# PRE_amp_22_5.net
KiCad netlist of a schematic drawn in EAGLE
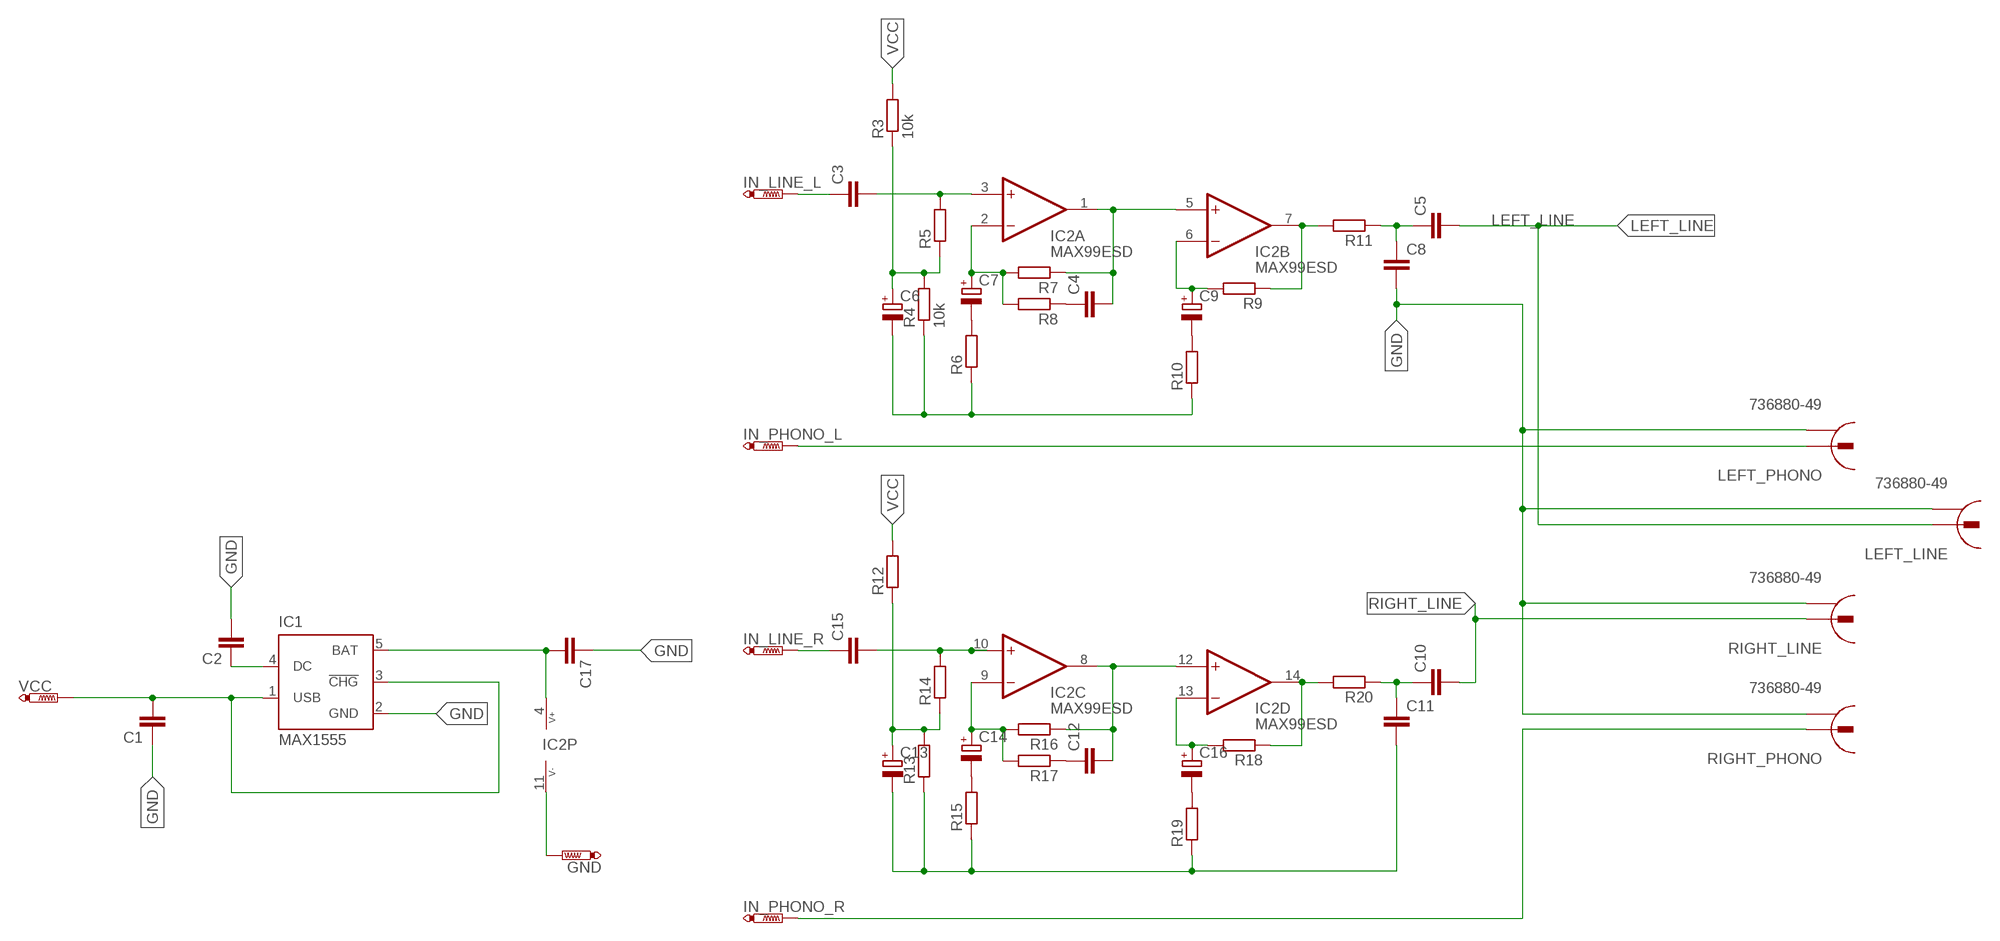
[diagram p0: schematic, sheet 1]

(export (version "E")
  (design (tool "Eeschema 10.0.6"))
  (components
    (comp (ref "C1")
      (value "C-EUC0805")
      (footprint "eagle-import:C0805")
      (libsource (lib "eagle-import") (part "C-EUC0805"))
    )
    (comp (ref "C2")
      (value "C-EUC0805")
      (footprint "eagle-import:C0805")
      (libsource (lib "eagle-import") (part "C-EUC0805"))
    )
    (comp (ref "C3")
      (value "C-EUC0805")
      (footprint "eagle-import:C0805")
      (libsource (lib "eagle-import") (part "C-EUC0805"))
    )
    (comp (ref "C4")
      (value "C-EUC0805")
      (footprint "eagle-import:C0805")
      (libsource (lib "eagle-import") (part "C-EUC0805"))
    )
    (comp (ref "C5")
      (value "C-EUC0805")
      (footprint "eagle-import:C0805")
      (libsource (lib "eagle-import") (part "C-EUC0805"))
    )
    (comp (ref "C6")
      (value "CPOL-EUB45181B")
      (footprint "eagle-import:B45181B")
      (libsource (lib "eagle-import") (part "CPOL-EUB45181B"))
    )
    (comp (ref "C7")
      (value "CPOL-EUB45181B")
      (footprint "eagle-import:B45181B")
      (libsource (lib "eagle-import") (part "CPOL-EUB45181B"))
    )
    (comp (ref "C8")
      (value "C-EUC0805")
      (footprint "eagle-import:C0805")
      (libsource (lib "eagle-import") (part "C-EUC0805"))
    )
    (comp (ref "C9")
      (value "CPOL-EUB45181B")
      (footprint "eagle-import:B45181B")
      (libsource (lib "eagle-import") (part "CPOL-EUB45181B"))
    )
    (comp (ref "C10")
      (value "C-EUC0805")
      (footprint "eagle-import:C0805")
      (libsource (lib "eagle-import") (part "C-EUC0805"))
    )
    (comp (ref "C11")
      (value "C-EUC0805")
      (footprint "eagle-import:C0805")
      (libsource (lib "eagle-import") (part "C-EUC0805"))
    )
    (comp (ref "C12")
      (value "C-EUC0805")
      (footprint "eagle-import:C0805")
      (libsource (lib "eagle-import") (part "C-EUC0805"))
    )
    (comp (ref "C13")
      (value "CPOL-EUB45181B")
      (footprint "eagle-import:B45181B")
      (libsource (lib "eagle-import") (part "CPOL-EUB45181B"))
    )
    (comp (ref "C14")
      (value "CPOL-EUB45181B")
      (footprint "eagle-import:B45181B")
      (libsource (lib "eagle-import") (part "CPOL-EUB45181B"))
    )
    (comp (ref "C15")
      (value "C-EUC0805")
      (footprint "eagle-import:C0805")
      (libsource (lib "eagle-import") (part "C-EUC0805"))
    )
    (comp (ref "C16")
      (value "CPOL-EUB45181B")
      (footprint "eagle-import:B45181B")
      (libsource (lib "eagle-import") (part "CPOL-EUB45181B"))
    )
    (comp (ref "C17")
      (value "C-EUC0805")
      (footprint "eagle-import:C0805")
      (libsource (lib "eagle-import") (part "C-EUC0805"))
    )
    (comp (ref "GND")
      (value "PTR1PAD1-13Y")
      (footprint "eagle-import:P1-13Y")
      (libsource (lib "eagle-import") (part "PTR1PAD1-13Y"))
    )
    (comp (ref "IC1")
      (value "MAX1555")
      (footprint "eagle-import:SOT23-5L")
      (libsource (lib "eagle-import") (part "MAX1555"))
    )
    (comp (ref "IC2")
      (value "MAX99ESD")
      (footprint "eagle-import:SO14")
      (libsource (lib "eagle-import") (part "MAX99ESD"))
    )
    (comp (ref "IN_LINE_L")
      (value "PTR1PAD1-13Y")
      (footprint "eagle-import:P1-13Y")
      (libsource (lib "eagle-import") (part "PTR1PAD1-13Y"))
    )
    (comp (ref "IN_LINE_R")
      (value "PTR1PAD1-13Y")
      (footprint "eagle-import:P1-13Y")
      (libsource (lib "eagle-import") (part "PTR1PAD1-13Y"))
    )
    (comp (ref "IN_PHONO_L")
      (value "PTR1PAD1-13Y")
      (footprint "eagle-import:P1-13Y")
      (libsource (lib "eagle-import") (part "PTR1PAD1-13Y"))
    )
    (comp (ref "IN_PHONO_R")
      (value "PTR1PAD1-13Y")
      (footprint "eagle-import:P1-13Y")
      (libsource (lib "eagle-import") (part "PTR1PAD1-13Y"))
    )
    (comp (ref "LEFT_LINE")
      (value "736880-49")
      (footprint "eagle-import:736880-49")
      (libsource (lib "eagle-import") (part "736880-49"))
    )
    (comp (ref "LEFT_PHONO")
      (value "736880-49")
      (footprint "eagle-import:736880-49")
      (libsource (lib "eagle-import") (part "736880-49"))
    )
    (comp (ref "R3")
      (value "10k")
      (footprint "eagle-import:R1206")
      (libsource (lib "eagle-import") (part "R-EU_R1206"))
    )
    (comp (ref "R4")
      (value "10k")
      (footprint "eagle-import:R1206")
      (libsource (lib "eagle-import") (part "R-EU_R1206"))
    )
    (comp (ref "R5")
      (value "R-EU_R1206")
      (footprint "eagle-import:R1206")
      (libsource (lib "eagle-import") (part "R-EU_R1206"))
    )
    (comp (ref "R6")
      (value "R-EU_R1206")
      (footprint "eagle-import:R1206")
      (libsource (lib "eagle-import") (part "R-EU_R1206"))
    )
    (comp (ref "R7")
      (value "R-EU_R1206")
      (footprint "eagle-import:R1206")
      (libsource (lib "eagle-import") (part "R-EU_R1206"))
    )
    (comp (ref "R8")
      (value "R-EU_R1206")
      (footprint "eagle-import:R1206")
      (libsource (lib "eagle-import") (part "R-EU_R1206"))
    )
    (comp (ref "R9")
      (value "R-EU_R1206")
      (footprint "eagle-import:R1206")
      (libsource (lib "eagle-import") (part "R-EU_R1206"))
    )
    (comp (ref "R10")
      (value "R-EU_R1206")
      (footprint "eagle-import:R1206")
      (libsource (lib "eagle-import") (part "R-EU_R1206"))
    )
    (comp (ref "R11")
      (value "R-EU_R1206")
      (footprint "eagle-import:R1206")
      (libsource (lib "eagle-import") (part "R-EU_R1206"))
    )
    (comp (ref "R12")
      (value "R-EU_R1206")
      (footprint "eagle-import:R1206")
      (libsource (lib "eagle-import") (part "R-EU_R1206"))
    )
    (comp (ref "R13")
      (value "R-EU_R1206")
      (footprint "eagle-import:R1206")
      (libsource (lib "eagle-import") (part "R-EU_R1206"))
    )
    (comp (ref "R14")
      (value "R-EU_R1206")
      (footprint "eagle-import:R1206")
      (libsource (lib "eagle-import") (part "R-EU_R1206"))
    )
    (comp (ref "R15")
      (value "R-EU_R1206")
      (footprint "eagle-import:R1206")
      (libsource (lib "eagle-import") (part "R-EU_R1206"))
    )
    (comp (ref "R16")
      (value "R-EU_R1206")
      (footprint "eagle-import:R1206")
      (libsource (lib "eagle-import") (part "R-EU_R1206"))
    )
    (comp (ref "R17")
      (value "R-EU_R1206")
      (footprint "eagle-import:R1206")
      (libsource (lib "eagle-import") (part "R-EU_R1206"))
    )
    (comp (ref "R18")
      (value "R-EU_R1206")
      (footprint "eagle-import:R1206")
      (libsource (lib "eagle-import") (part "R-EU_R1206"))
    )
    (comp (ref "R19")
      (value "R-EU_R1206")
      (footprint "eagle-import:R1206")
      (libsource (lib "eagle-import") (part "R-EU_R1206"))
    )
    (comp (ref "R20")
      (value "R-EU_R1206")
      (footprint "eagle-import:R1206")
      (libsource (lib "eagle-import") (part "R-EU_R1206"))
    )
    (comp (ref "RIGHT_LINE")
      (value "736880-49")
      (footprint "eagle-import:736880-49")
      (libsource (lib "eagle-import") (part "736880-49"))
    )
    (comp (ref "RIGHT_PHONO")
      (value "736880-49")
      (footprint "eagle-import:736880-49")
      (libsource (lib "eagle-import") (part "736880-49"))
    )
    (comp (ref "VCC")
      (value "PTR1PAD1-13Y")
      (footprint "eagle-import:P1-13Y")
      (libsource (lib "eagle-import") (part "PTR1PAD1-13Y"))
    )
  )
  (nets
    (net (code "1") (name "GND") (class "Default")
      (node (ref "C1") (pin "1") (pinfunction "1_1") (pintype "passive"))
      (node (ref "C11") (pin "2") (pinfunction "2_2") (pintype "passive"))
      (node (ref "C13") (pin "-") (pinfunction "-_-") (pintype "passive"))
      (node (ref "C17") (pin "1") (pinfunction "1_1") (pintype "passive"))
      (node (ref "C2") (pin "2") (pinfunction "2_2") (pintype "passive"))
      (node (ref "C6") (pin "-") (pinfunction "-_-") (pintype "passive"))
      (node (ref "C8") (pin "2") (pinfunction "2_2") (pintype "passive"))
      (node (ref "GND") (pin "1") (pinfunction "TP_1") (pintype "input"))
      (node (ref "IC1") (pin "2") (pinfunction "GND_2") (pintype "power_in"))
      (node (ref "IC2") (pin "11") (pinfunction "V-_11") (pintype "power_in"))
      (node (ref "LEFT_LINE") (pin "2") (pinfunction "2_2") (pintype "passive"))
      (node (ref "LEFT_PHONO") (pin "2") (pinfunction "2_2") (pintype "passive"))
      (node (ref "R10") (pin "1") (pinfunction "1_1") (pintype "passive"))
      (node (ref "R13") (pin "1") (pinfunction "1_1") (pintype "passive"))
      (node (ref "R15") (pin "1") (pinfunction "1_1") (pintype "passive"))
      (node (ref "R19") (pin "1") (pinfunction "1_1") (pintype "passive"))
      (node (ref "R4") (pin "1") (pinfunction "1_1") (pintype "passive"))
      (node (ref "R6") (pin "1") (pinfunction "1_1") (pintype "passive"))
      (node (ref "RIGHT_LINE") (pin "2") (pinfunction "2_2") (pintype "passive"))
      (node (ref "RIGHT_PHONO") (pin "2") (pinfunction "2_2") (pintype "passive"))
    )
    (net (code "2") (name "LEFT_LINE") (class "Default")
      (node (ref "C5") (pin "2") (pinfunction "2_2") (pintype "passive"))
      (node (ref "LEFT_LINE") (pin "1") (pinfunction "1_1") (pintype "passive"))
    )
    (net (code "3") (name "Net-(C4-Pad1)") (class "Default")
      (node (ref "C4") (pin "1") (pinfunction "1_1") (pintype "passive"))
      (node (ref "R8") (pin "1") (pinfunction "1_1") (pintype "passive"))
    )
    (net (code "4") (name "Net-(C5-Pad1)") (class "Default")
      (node (ref "C5") (pin "1") (pinfunction "1_1") (pintype "passive"))
      (node (ref "C8") (pin "1") (pinfunction "1_1") (pintype "passive"))
      (node (ref "R11") (pin "1") (pinfunction "1_1") (pintype "passive"))
    )
    (net (code "5") (name "Net-(C6-Pad+)") (class "Default")
      (node (ref "C6") (pin "+") (pinfunction "+_+") (pintype "passive"))
      (node (ref "R3") (pin "1") (pinfunction "1_1") (pintype "passive"))
      (node (ref "R4") (pin "2") (pinfunction "2_2") (pintype "passive"))
      (node (ref "R5") (pin "1") (pinfunction "1_1") (pintype "passive"))
    )
    (net (code "6") (name "Net-(C7-Pad-)") (class "Default")
      (node (ref "C7") (pin "-") (pinfunction "-_-") (pintype "passive"))
      (node (ref "R6") (pin "2") (pinfunction "2_2") (pintype "passive"))
    )
    (net (code "7") (name "Net-(C9-Pad-)") (class "Default")
      (node (ref "C9") (pin "-") (pinfunction "-_-") (pintype "passive"))
      (node (ref "R10") (pin "2") (pinfunction "2_2") (pintype "passive"))
    )
    (net (code "8") (name "Net-(C10-Pad1)") (class "Default")
      (node (ref "C10") (pin "1") (pinfunction "1_1") (pintype "passive"))
      (node (ref "C11") (pin "1") (pinfunction "1_1") (pintype "passive"))
      (node (ref "R20") (pin "1") (pinfunction "1_1") (pintype "passive"))
    )
    (net (code "9") (name "Net-(C12-Pad1)") (class "Default")
      (node (ref "C12") (pin "1") (pinfunction "1_1") (pintype "passive"))
      (node (ref "R17") (pin "1") (pinfunction "1_1") (pintype "passive"))
    )
    (net (code "10") (name "Net-(C13-Pad+)") (class "Default")
      (node (ref "C13") (pin "+") (pinfunction "+_+") (pintype "passive"))
      (node (ref "R12") (pin "1") (pinfunction "1_1") (pintype "passive"))
      (node (ref "R13") (pin "2") (pinfunction "2_2") (pintype "passive"))
      (node (ref "R14") (pin "1") (pinfunction "1_1") (pintype "passive"))
    )
    (net (code "11") (name "Net-(C14-Pad-)") (class "Default")
      (node (ref "C14") (pin "-") (pinfunction "-_-") (pintype "passive"))
      (node (ref "R15") (pin "2") (pinfunction "2_2") (pintype "passive"))
    )
    (net (code "12") (name "Net-(C16-Pad-)") (class "Default")
      (node (ref "C16") (pin "-") (pinfunction "-_-") (pintype "passive"))
      (node (ref "R19") (pin "2") (pinfunction "2_2") (pintype "passive"))
    )
    (net (code "13") (name "Net-(IC1-BAT)") (class "Default")
      (node (ref "C17") (pin "2") (pinfunction "2_2") (pintype "passive"))
      (node (ref "IC1") (pin "5") (pinfunction "BAT_5") (pintype "passive"))
      (node (ref "IC2") (pin "4") (pinfunction "V+_4") (pintype "power_in"))
    )
    (net (code "14") (name "Net-(IC1-DC)") (class "Default")
      (node (ref "C2") (pin "1") (pinfunction "1_1") (pintype "passive"))
      (node (ref "IC1") (pin "4") (pinfunction "DC_4") (pintype "input"))
    )
    (net (code "15") (name "Net-(IC1-USB)") (class "Default")
      (node (ref "C1") (pin "2") (pinfunction "2_2") (pintype "passive"))
      (node (ref "IC1") (pin "1") (pinfunction "USB_1") (pintype "input"))
      (node (ref "IC1") (pin "3") (pinfunction "~{CHG}_3") (pintype "output"))
      (node (ref "VCC") (pin "1") (pinfunction "TP_1") (pintype "input"))
    )
    (net (code "16") (name "Net-(IC2A-+IN)") (class "Default")
      (node (ref "C3") (pin "2") (pinfunction "2_2") (pintype "passive"))
      (node (ref "IC2") (pin "3") (pinfunction "+IN_3") (pintype "input"))
      (node (ref "R5") (pin "2") (pinfunction "2_2") (pintype "passive"))
    )
    (net (code "17") (name "Net-(IC2A--IN)") (class "Default")
      (node (ref "C7") (pin "+") (pinfunction "+_+") (pintype "passive"))
      (node (ref "IC2") (pin "2") (pinfunction "-IN_2") (pintype "input"))
      (node (ref "R7") (pin "2") (pinfunction "2_2") (pintype "passive"))
      (node (ref "R8") (pin "2") (pinfunction "2_2") (pintype "passive"))
    )
    (net (code "18") (name "Net-(IC2A-OUT)") (class "Default")
      (node (ref "C4") (pin "2") (pinfunction "2_2") (pintype "passive"))
      (node (ref "IC2") (pin "1") (pinfunction "OUT_1") (pintype "output"))
      (node (ref "IC2") (pin "5") (pinfunction "+IN_5") (pintype "input"))
      (node (ref "R7") (pin "1") (pinfunction "1_1") (pintype "passive"))
    )
    (net (code "19") (name "Net-(IC2B--IN)") (class "Default")
      (node (ref "C9") (pin "+") (pinfunction "+_+") (pintype "passive"))
      (node (ref "IC2") (pin "6") (pinfunction "-IN_6") (pintype "input"))
      (node (ref "R9") (pin "2") (pinfunction "2_2") (pintype "passive"))
    )
    (net (code "20") (name "Net-(IC2B-OUT)") (class "Default")
      (node (ref "IC2") (pin "7") (pinfunction "OUT_7") (pintype "output"))
      (node (ref "R11") (pin "2") (pinfunction "2_2") (pintype "passive"))
      (node (ref "R9") (pin "1") (pinfunction "1_1") (pintype "passive"))
    )
    (net (code "21") (name "Net-(IC2C-+IN)") (class "Default")
      (node (ref "C15") (pin "2") (pinfunction "2_2") (pintype "passive"))
      (node (ref "IC2") (pin "10") (pinfunction "+IN_10") (pintype "input"))
      (node (ref "R14") (pin "2") (pinfunction "2_2") (pintype "passive"))
    )
    (net (code "22") (name "Net-(IC2C--IN)") (class "Default")
      (node (ref "C14") (pin "+") (pinfunction "+_+") (pintype "passive"))
      (node (ref "IC2") (pin "9") (pinfunction "-IN_9") (pintype "input"))
      (node (ref "R16") (pin "2") (pinfunction "2_2") (pintype "passive"))
      (node (ref "R17") (pin "2") (pinfunction "2_2") (pintype "passive"))
    )
    (net (code "23") (name "Net-(IC2C-OUT)") (class "Default")
      (node (ref "C12") (pin "2") (pinfunction "2_2") (pintype "passive"))
      (node (ref "IC2") (pin "12") (pinfunction "+IN_12") (pintype "input"))
      (node (ref "IC2") (pin "8") (pinfunction "OUT_8") (pintype "output"))
      (node (ref "R16") (pin "1") (pinfunction "1_1") (pintype "passive"))
    )
    (net (code "24") (name "Net-(IC2D--IN)") (class "Default")
      (node (ref "C16") (pin "+") (pinfunction "+_+") (pintype "passive"))
      (node (ref "IC2") (pin "13") (pinfunction "-IN_13") (pintype "input"))
      (node (ref "R18") (pin "2") (pinfunction "2_2") (pintype "passive"))
    )
    (net (code "25") (name "Net-(IC2D-OUT)") (class "Default")
      (node (ref "IC2") (pin "14") (pinfunction "OUT_14") (pintype "output"))
      (node (ref "R18") (pin "1") (pinfunction "1_1") (pintype "passive"))
      (node (ref "R20") (pin "2") (pinfunction "2_2") (pintype "passive"))
    )
    (net (code "26") (name "Net-(IN_LINE_L-TP)") (class "Default")
      (node (ref "C3") (pin "1") (pinfunction "1_1") (pintype "passive"))
      (node (ref "IN_LINE_L") (pin "1") (pinfunction "TP_1") (pintype "input"))
    )
    (net (code "27") (name "Net-(IN_LINE_R-TP)") (class "Default")
      (node (ref "C15") (pin "1") (pinfunction "1_1") (pintype "passive"))
      (node (ref "IN_LINE_R") (pin "1") (pinfunction "TP_1") (pintype "input"))
    )
    (net (code "28") (name "Net-(IN_PHONO_L-TP)") (class "Default")
      (node (ref "IN_PHONO_L") (pin "1") (pinfunction "TP_1") (pintype "input"))
      (node (ref "LEFT_PHONO") (pin "1") (pinfunction "1_1") (pintype "passive"))
    )
    (net (code "29") (name "Net-(IN_PHONO_R-TP)") (class "Default")
      (node (ref "IN_PHONO_R") (pin "1") (pinfunction "TP_1") (pintype "input"))
      (node (ref "RIGHT_PHONO") (pin "1") (pinfunction "1_1") (pintype "passive"))
    )
    (net (code "30") (name "RIGHT_LINE") (class "Default")
      (node (ref "C10") (pin "2") (pinfunction "2_2") (pintype "passive"))
      (node (ref "RIGHT_LINE") (pin "1") (pinfunction "1_1") (pintype "passive"))
    )
    (net (code "31") (name "VCC") (class "Default")
      (node (ref "R12") (pin "2") (pinfunction "2_2") (pintype "passive"))
      (node (ref "R3") (pin "2") (pinfunction "2_2") (pintype "passive"))
    )
    (net (code "32") (name "unconnected-(LEFT_LINE-2-Pad2@2)") (class "Default")
      (node (ref "LEFT_LINE") (pin "2@2") (pinfunction "2_2@2") (pintype "passive"))
    )
    (net (code "33") (name "unconnected-(LEFT_PHONO-2-Pad2@2)") (class "Default")
      (node (ref "LEFT_PHONO") (pin "2@2") (pinfunction "2_2@2") (pintype "passive"))
    )
    (net (code "34") (name "unconnected-(RIGHT_LINE-2-Pad2@2)") (class "Default")
      (node (ref "RIGHT_LINE") (pin "2@2") (pinfunction "2_2@2") (pintype "passive"))
    )
    (net (code "35") (name "unconnected-(RIGHT_PHONO-2-Pad2@2)") (class "Default")
      (node (ref "RIGHT_PHONO") (pin "2@2") (pinfunction "2_2@2") (pintype "passive"))
    )
  )
)
